# BALPGAS.net
KiCad netlist of a schematic drawn in EAGLE
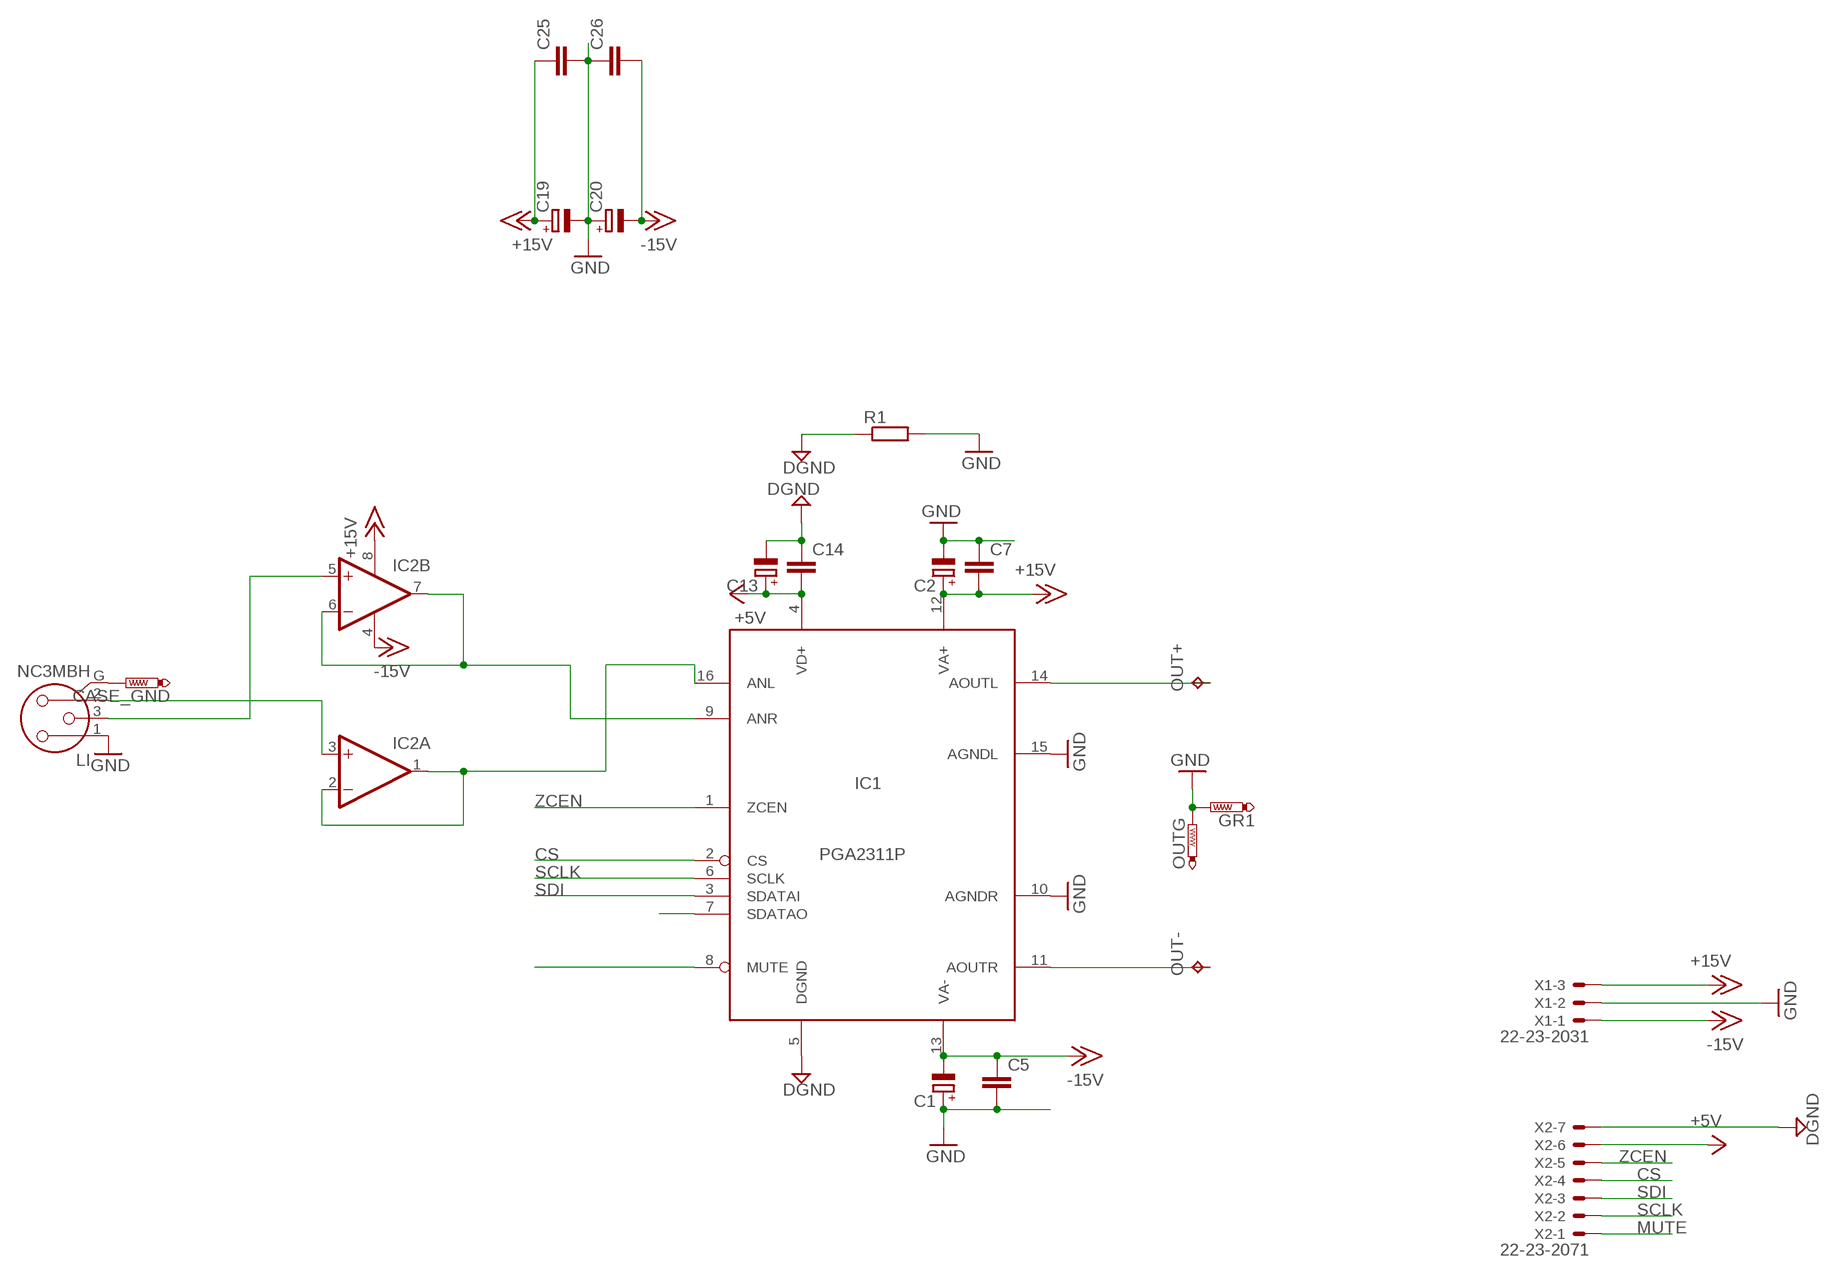
[diagram p0: schematic, sheet 1]

(export (version "E")
  (design (tool "Eeschema 10.0.6"))
  (components
    (comp (ref "C1")
      (value "CPOL-EUE5-10.5")
      (footprint "eagle-import:E5-10,5")
      (libsource (lib "eagle-import") (part "CPOL-EUE5-10.5"))
    )
    (comp (ref "C2")
      (value "CPOL-EUE5-10.5")
      (footprint "eagle-import:E5-10,5")
      (libsource (lib "eagle-import") (part "CPOL-EUE5-10.5"))
    )
    (comp (ref "C5")
      (value "C-EU050-045X075")
      (footprint "eagle-import:C050-045X075")
      (libsource (lib "eagle-import") (part "C-EU050-045X075"))
    )
    (comp (ref "C7")
      (value "C-EU050-045X075")
      (footprint "eagle-import:C050-045X075")
      (libsource (lib "eagle-import") (part "C-EU050-045X075"))
    )
    (comp (ref "C13")
      (value "CPOL-EUSMCD")
      (footprint "eagle-import:SMC_D")
      (libsource (lib "eagle-import") (part "resistor_CPOL-EUSMCD"))
    )
    (comp (ref "C14")
      (value "C-EUC1206")
      (footprint "eagle-import:C1206")
      (libsource (lib "eagle-import") (part "resistor_C-EUC1206"))
    )
    (comp (ref "C19")
      (value "CPOL-EUE5-10.5")
      (footprint "eagle-import:E5-10,5")
      (libsource (lib "eagle-import") (part "CPOL-EUE5-10.5"))
    )
    (comp (ref "C20")
      (value "CPOL-EUE5-10.5")
      (footprint "eagle-import:E5-10,5")
      (libsource (lib "eagle-import") (part "CPOL-EUE5-10.5"))
    )
    (comp (ref "C25")
      (value "C-EU050-045X075")
      (footprint "eagle-import:C050-045X075")
      (libsource (lib "eagle-import") (part "C-EU050-045X075"))
    )
    (comp (ref "C26")
      (value "C-EU050-045X075")
      (footprint "eagle-import:C050-045X075")
      (libsource (lib "eagle-import") (part "C-EU050-045X075"))
    )
    (comp (ref "CASE_GND")
      (value "PTR1PAD1-17")
      (footprint "eagle-import:P1-17")
      (libsource (lib "eagle-import") (part "PTR1PAD1-17"))
    )
    (comp (ref "GR1")
      (value "PTR1PAD1-17")
      (footprint "eagle-import:P1-17")
      (libsource (lib "eagle-import") (part "PTR1PAD1-17"))
    )
    (comp (ref "IC1")
      (value "PGA2311P")
      (footprint "eagle-import:DIL16")
      (libsource (lib "eagle-import") (part "PGA2311P"))
    )
    (comp (ref "IC2")
      (value "2AMP_P8+4N")
      (footprint "eagle-import:DIL08")
      (libsource (lib "eagle-import") (part "2AMP_P8+4N"))
    )
    (comp (ref "LI")
      (value "NC3MBH")
      (footprint "eagle-import:NC3MBH")
      (fields (field (name "MF") "NEUTRIK"))
      (libsource (lib "eagle-import") (part "NC3MBH"))
    )
    (comp (ref "OUT+")
      (value "TPPAD1-20")
      (footprint "eagle-import:P1-20")
      (libsource (lib "eagle-import") (part "TPPAD1-20"))
    )
    (comp (ref "OUT-")
      (value "TPPAD1-20")
      (footprint "eagle-import:P1-20")
      (libsource (lib "eagle-import") (part "TPPAD1-20"))
    )
    (comp (ref "OUTG")
      (value "PTR1PAD1-17")
      (footprint "eagle-import:P1-17")
      (libsource (lib "eagle-import") (part "PTR1PAD1-17"))
    )
    (comp (ref "R1")
      (value "R-EU_0207/10")
      (footprint "eagle-import:0207_10")
      (libsource (lib "eagle-import") (part "R-EU_0207/10"))
    )
    (comp (ref "X1")
      (value "22-23-2031")
      (footprint "eagle-import:22-23-2031")
      (fields (field (name "MF") "MOLEX"))
      (libsource (lib "eagle-import") (part "22-23-2031"))
    )
    (comp (ref "X2")
      (value "22-23-2071")
      (footprint "eagle-import:22-23-2071")
      (fields (field (name "MF") "MOLEX"))
      (libsource (lib "eagle-import") (part "22-23-2071"))
    )
  )
  (nets
    (net (code "1") (name "+5V") (class "Default")
      (node (ref "C13") (pin "+") (pinfunction "+_+") (pintype "passive"))
      (node (ref "C14") (pin "2") (pinfunction "2_2") (pintype "passive"))
      (node (ref "IC1") (pin "4") (pinfunction "VD+_4") (pintype "power_in"))
      (node (ref "X2") (pin "6") (pinfunction "S_6") (pintype "passive"))
    )
    (net (code "2") (name "+15V") (class "Default")
      (node (ref "C19") (pin "+") (pinfunction "+_+") (pintype "passive"))
      (node (ref "C2") (pin "+") (pinfunction "+_+") (pintype "passive"))
      (node (ref "C25") (pin "1") (pinfunction "1_1") (pintype "passive"))
      (node (ref "C7") (pin "2") (pinfunction "2_2") (pintype "passive"))
      (node (ref "IC1") (pin "12") (pinfunction "VA+_12") (pintype "power_in"))
      (node (ref "IC2") (pin "8") (pinfunction "V+_8") (pintype "power_in"))
      (node (ref "X1") (pin "3") (pinfunction "S_3") (pintype "passive"))
    )
    (net (code "3") (name "-15V") (class "Default")
      (node (ref "C1") (pin "-") (pinfunction "-_-") (pintype "passive"))
      (node (ref "C20") (pin "-") (pinfunction "-_-") (pintype "passive"))
      (node (ref "C26") (pin "2") (pinfunction "2_2") (pintype "passive"))
      (node (ref "C5") (pin "1") (pinfunction "1_1") (pintype "passive"))
      (node (ref "IC1") (pin "13") (pinfunction "VA-_13") (pintype "power_in"))
      (node (ref "IC2") (pin "4") (pinfunction "V-_4") (pintype "power_in"))
      (node (ref "X1") (pin "1") (pinfunction "S_1") (pintype "passive"))
    )
    (net (code "4") (name "/CS") (class "Default")
      (node (ref "IC1") (pin "2") (pinfunction "CS_2") (pintype "input"))
      (node (ref "X2") (pin "4") (pinfunction "S_4") (pintype "passive"))
    )
    (net (code "5") (name "/MUTE") (class "Default")
      (node (ref "IC1") (pin "8") (pinfunction "MUTE_8") (pintype "input"))
      (node (ref "X2") (pin "1") (pinfunction "S_1") (pintype "passive"))
    )
    (net (code "6") (name "/SCLK") (class "Default")
      (node (ref "IC1") (pin "6") (pinfunction "SCLK_6") (pintype "input"))
      (node (ref "X2") (pin "2") (pinfunction "S_2") (pintype "passive"))
    )
    (net (code "7") (name "/SDI") (class "Default")
      (node (ref "IC1") (pin "3") (pinfunction "SDATAI_3") (pintype "input"))
      (node (ref "X2") (pin "3") (pinfunction "S_3") (pintype "passive"))
    )
    (net (code "8") (name "/ZCEN") (class "Default")
      (node (ref "IC1") (pin "1") (pinfunction "ZCEN_1") (pintype "input"))
      (node (ref "X2") (pin "5") (pinfunction "S_5") (pintype "passive"))
    )
    (net (code "9") (name "DGND") (class "Default")
      (node (ref "C13") (pin "-") (pinfunction "-_-") (pintype "passive"))
      (node (ref "C14") (pin "1") (pinfunction "1_1") (pintype "passive"))
      (node (ref "IC1") (pin "5") (pinfunction "DGND_5") (pintype "power_in"))
      (node (ref "R1") (pin "1") (pinfunction "1_1") (pintype "passive"))
      (node (ref "X2") (pin "7") (pinfunction "S_7") (pintype "passive"))
    )
    (net (code "10") (name "GND") (class "Default")
      (node (ref "C1") (pin "+") (pinfunction "+_+") (pintype "passive"))
      (node (ref "C19") (pin "-") (pinfunction "-_-") (pintype "passive"))
      (node (ref "C2") (pin "-") (pinfunction "-_-") (pintype "passive"))
      (node (ref "C20") (pin "+") (pinfunction "+_+") (pintype "passive"))
      (node (ref "C25") (pin "2") (pinfunction "2_2") (pintype "passive"))
      (node (ref "C26") (pin "1") (pinfunction "1_1") (pintype "passive"))
      (node (ref "C5") (pin "2") (pinfunction "2_2") (pintype "passive"))
      (node (ref "C7") (pin "1") (pinfunction "1_1") (pintype "passive"))
      (node (ref "GR1") (pin "TP") (pinfunction "TP_TP") (pintype "input"))
      (node (ref "IC1") (pin "10") (pinfunction "AGNDR_10") (pintype "power_in"))
      (node (ref "IC1") (pin "15") (pinfunction "AGNDL_15") (pintype "power_in"))
      (node (ref "LI") (pin "1") (pinfunction "1_1") (pintype "passive"))
      (node (ref "OUTG") (pin "TP") (pinfunction "TP_TP") (pintype "input"))
      (node (ref "R1") (pin "2") (pinfunction "2_2") (pintype "passive"))
      (node (ref "X1") (pin "2") (pinfunction "S_2") (pintype "passive"))
    )
    (net (code "11") (name "Net-(CASE_GND-PadTP)") (class "Default")
      (node (ref "CASE_GND") (pin "TP") (pinfunction "TP_TP") (pintype "input"))
      (node (ref "LI") (pin "G") (pinfunction "G_G") (pintype "passive"))
    )
    (net (code "12") (name "Net-(IC1-ANL)") (class "Default")
      (node (ref "IC1") (pin "16") (pinfunction "ANL_16") (pintype "input"))
      (node (ref "IC2") (pin "1") (pinfunction "OUT_1") (pintype "output"))
      (node (ref "IC2") (pin "2") (pinfunction "-IN_2") (pintype "input"))
    )
    (net (code "13") (name "Net-(IC1-ANR)") (class "Default")
      (node (ref "IC1") (pin "9") (pinfunction "ANR_9") (pintype "input"))
      (node (ref "IC2") (pin "6") (pinfunction "-IN_6") (pintype "input"))
      (node (ref "IC2") (pin "7") (pinfunction "OUT_7") (pintype "output"))
    )
    (net (code "14") (name "Net-(IC1-AOUTL)") (class "Default")
      (node (ref "IC1") (pin "14") (pinfunction "AOUTL_14") (pintype "output"))
      (node (ref "OUT+") (pin "TP") (pinfunction "TP_TP") (pintype "input"))
    )
    (net (code "15") (name "Net-(IC1-AOUTR)") (class "Default")
      (node (ref "IC1") (pin "11") (pinfunction "AOUTR_11") (pintype "output"))
      (node (ref "OUT-") (pin "TP") (pinfunction "TP_TP") (pintype "input"))
    )
    (net (code "16") (name "Net-(IC2A-+IN)") (class "Default")
      (node (ref "IC2") (pin "3") (pinfunction "+IN_3") (pintype "input"))
      (node (ref "LI") (pin "2") (pinfunction "2_2") (pintype "passive"))
    )
    (net (code "17") (name "Net-(IC2B-+IN)") (class "Default")
      (node (ref "IC2") (pin "5") (pinfunction "+IN_5") (pintype "input"))
      (node (ref "LI") (pin "3") (pinfunction "3_3") (pintype "passive"))
    )
    (net (code "18") (name "unconnected-(IC1-SDATAO-Pad7)") (class "Default")
      (node (ref "IC1") (pin "7") (pinfunction "SDATAO_7") (pintype "output"))
    )
  )
)
